# Bank.net
KiCad netlist of a schematic drawn in Altium Designer
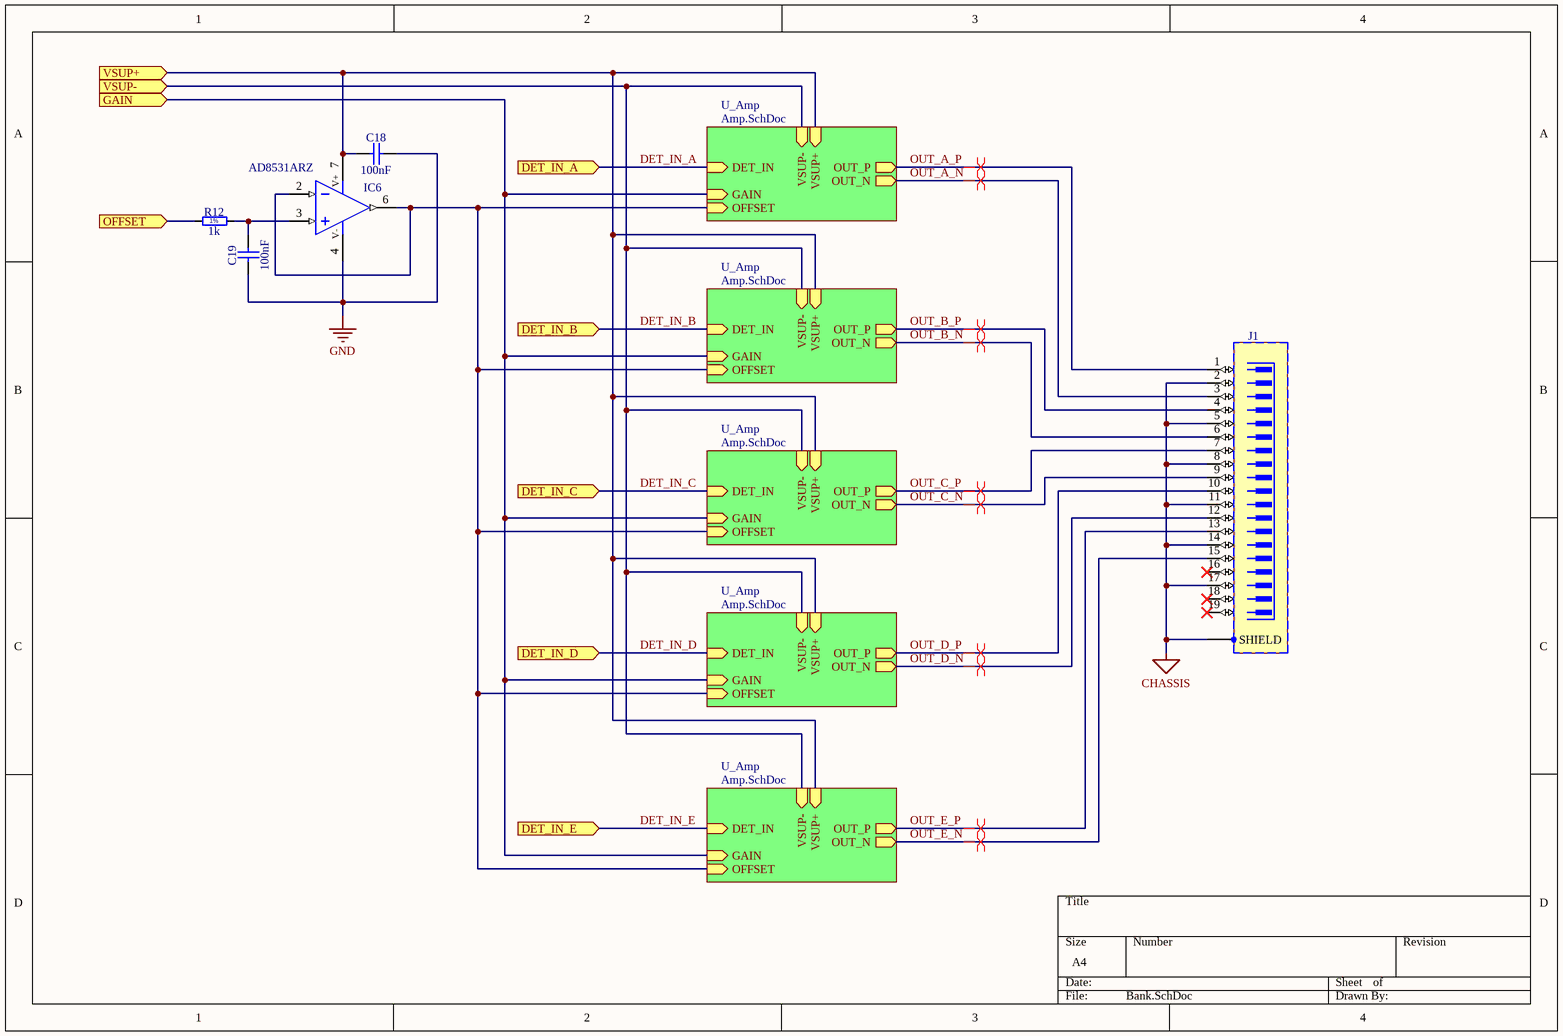
[diagram p0: Bank.SchDoc]

(export (version "E")
  (design (tool "Eeschema 10.0.6"))
  (components
    (comp (ref "C18")
      (value "100nF")
      (footprint "CAPC2012X135N")
      (description "Non-polarised capacitor")
      (fields
        (field (name "PART NUMBER") "CC0805_100NF_50V_10%_X7R")
        (field (name "VOLTAGE") "50V")
        (field (name "AUTHOR") "CERN DEM JLC")
      )
      (libsource (lib "Capacitors") (part "Capacitor - non polarized"))
    )
    (comp (ref "C19")
      (value "100nF")
      (footprint "CAPC2012X135N")
      (description "Non-polarised capacitor")
      (fields
        (field (name "PART NUMBER") "CC0805_100NF_50V_10%_X7R")
        (field (name "VOLTAGE") "50V")
        (field (name "AUTHOR") "CERN DEM JLC")
      )
      (libsource (lib "Capacitors") (part "Capacitor - non polarized"))
    )
    (comp (ref "IC6")
      (value "AD8531ARZ")
      (footprint "SOIC127P600X175-8N")
      (description "Operational Amplifier")
      (fields (field (name "MANUFACTURER") "ANALOG DEVICES") (field (name "AUTHOR") "CERN DEM JLC"))
      (libsource (lib "ICs And Semiconductors") (part "Operational Amplifier Type1"))
    )
    (comp (ref "J1")
      (value "HDMI")
      (footprint "TYCO_2007435-1")
      (description "Connector HDMI 19 Male + 1 Shield")
      (fields
        (field (name "PART NUMBER") "TYCO_2007435-1")
        (field (name "MANUFACTURER") "TYCO ELECTRONICS")
        (field (name "AUTHOR") "CERN DEM MR")
      )
      (libsource (lib "Connectors") (part "Connector HDMI 19 Male + 1 Shield"))
    )
    (comp (ref "R12")
      (value "1k")
      (footprint "RESC2012X60N")
      (description "Resistor - 1%")
      (fields
        (field (name "PART NUMBER") "R0805_1K_1%_0.125W_100PPM")
        (field (name "POWER") "0.125W")
        (field (name "AUTHOR") "CERN DEM JLC")
      )
      (libsource (lib "Resistors") (part "Resistor - 1%"))
    )
  )
  (nets
    (net (code "7") (name "/OFFSET") (class "Default")
      (node (ref "R12") (pin "1") (pinfunction "1_1") (pintype "passive"))
    )
    (net (code "8") (name "/OFFSET_1") (class "Default")
      (node (ref "IC6") (pin "2") (pinfunction "IN-_2") (pintype "input"))
      (node (ref "IC6") (pin "6") (pinfunction "OUT_6") (pintype "output"))
    )
    (net (code "9") (name "/OUT_A_N") (class "Default")
      (node (ref "J1") (pin "3") (pinfunction "3_3") (pintype "bidirectional"))
    )
    (net (code "10") (name "/OUT_A_P") (class "Default")
      (node (ref "J1") (pin "1") (pinfunction "1_1") (pintype "bidirectional"))
    )
    (net (code "11") (name "/OUT_B_N") (class "Default")
      (node (ref "J1") (pin "6") (pinfunction "6_6") (pintype "bidirectional"))
    )
    (net (code "12") (name "/OUT_B_P") (class "Default")
      (node (ref "J1") (pin "4") (pinfunction "4_4") (pintype "bidirectional"))
    )
    (net (code "13") (name "/OUT_C_N") (class "Default")
      (node (ref "J1") (pin "9") (pinfunction "9_9") (pintype "bidirectional"))
    )
    (net (code "14") (name "/OUT_C_P") (class "Default")
      (node (ref "J1") (pin "7") (pinfunction "7_7") (pintype "bidirectional"))
    )
    (net (code "15") (name "/OUT_D_N") (class "Default")
      (node (ref "J1") (pin "12") (pinfunction "12_12") (pintype "bidirectional"))
    )
    (net (code "16") (name "/OUT_D_P") (class "Default")
      (node (ref "J1") (pin "10") (pinfunction "10_10") (pintype "bidirectional"))
    )
    (net (code "17") (name "/OUT_E_N") (class "Default")
      (node (ref "J1") (pin "15") (pinfunction "15_15") (pintype "bidirectional"))
    )
    (net (code "18") (name "/OUT_E_P") (class "Default")
      (node (ref "J1") (pin "13") (pinfunction "13_13") (pintype "bidirectional"))
    )
    (net (code "19") (name "/VSUP+") (class "Default")
      (node (ref "C18") (pin "1") (pinfunction "1_1") (pintype "passive"))
      (node (ref "IC6") (pin "7") (pinfunction "V+_7") (pintype "power_in"))
    )
    (net (code "21") (name "CHASSIS") (class "Default")
      (node (ref "J1") (pin "11") (pinfunction "11_11") (pintype "bidirectional"))
      (node (ref "J1") (pin "14") (pinfunction "14_14") (pintype "bidirectional"))
      (node (ref "J1") (pin "17") (pinfunction "17_17") (pintype "bidirectional"))
      (node (ref "J1") (pin "2") (pinfunction "2_2") (pintype "bidirectional"))
      (node (ref "J1") (pin "5") (pinfunction "5_5") (pintype "bidirectional"))
      (node (ref "J1") (pin "8") (pinfunction "8_8") (pintype "bidirectional"))
      (node (ref "J1") (pin "SHIELD") (pinfunction "SHIELD_SHIELD") (pintype "power_in"))
    )
    (net (code "22") (name "GND") (class "Default")
      (node (ref "C18") (pin "2") (pinfunction "2_2") (pintype "passive"))
      (node (ref "C19") (pin "1") (pinfunction "1_1") (pintype "passive"))
      (node (ref "IC6") (pin "4") (pinfunction "V-_4") (pintype "power_in"))
    )
    (net (code "23") (name "Net-(IC6-IN+)") (class "Default")
      (node (ref "C19") (pin "2") (pinfunction "2_2") (pintype "passive"))
      (node (ref "IC6") (pin "3") (pinfunction "IN+_3") (pintype "input"))
      (node (ref "R12") (pin "2") (pinfunction "2_2") (pintype "passive"))
    )
    (net (code "24") (name "unconnected-(J1-Pad16)") (class "Default")
      (node (ref "J1") (pin "16") (pinfunction "16_16") (pintype "bidirectional+no_connect"))
    )
    (net (code "25") (name "unconnected-(J1-Pad18)") (class "Default")
      (node (ref "J1") (pin "18") (pinfunction "18_18") (pintype "bidirectional+no_connect"))
    )
    (net (code "26") (name "unconnected-(J1-Pad19)") (class "Default")
      (node (ref "J1") (pin "19") (pinfunction "19_19") (pintype "bidirectional+no_connect"))
    )
  )
)
